# rpi-adapter-board.net
KiCad netlist of a schematic drawn in EasyEDA Pro
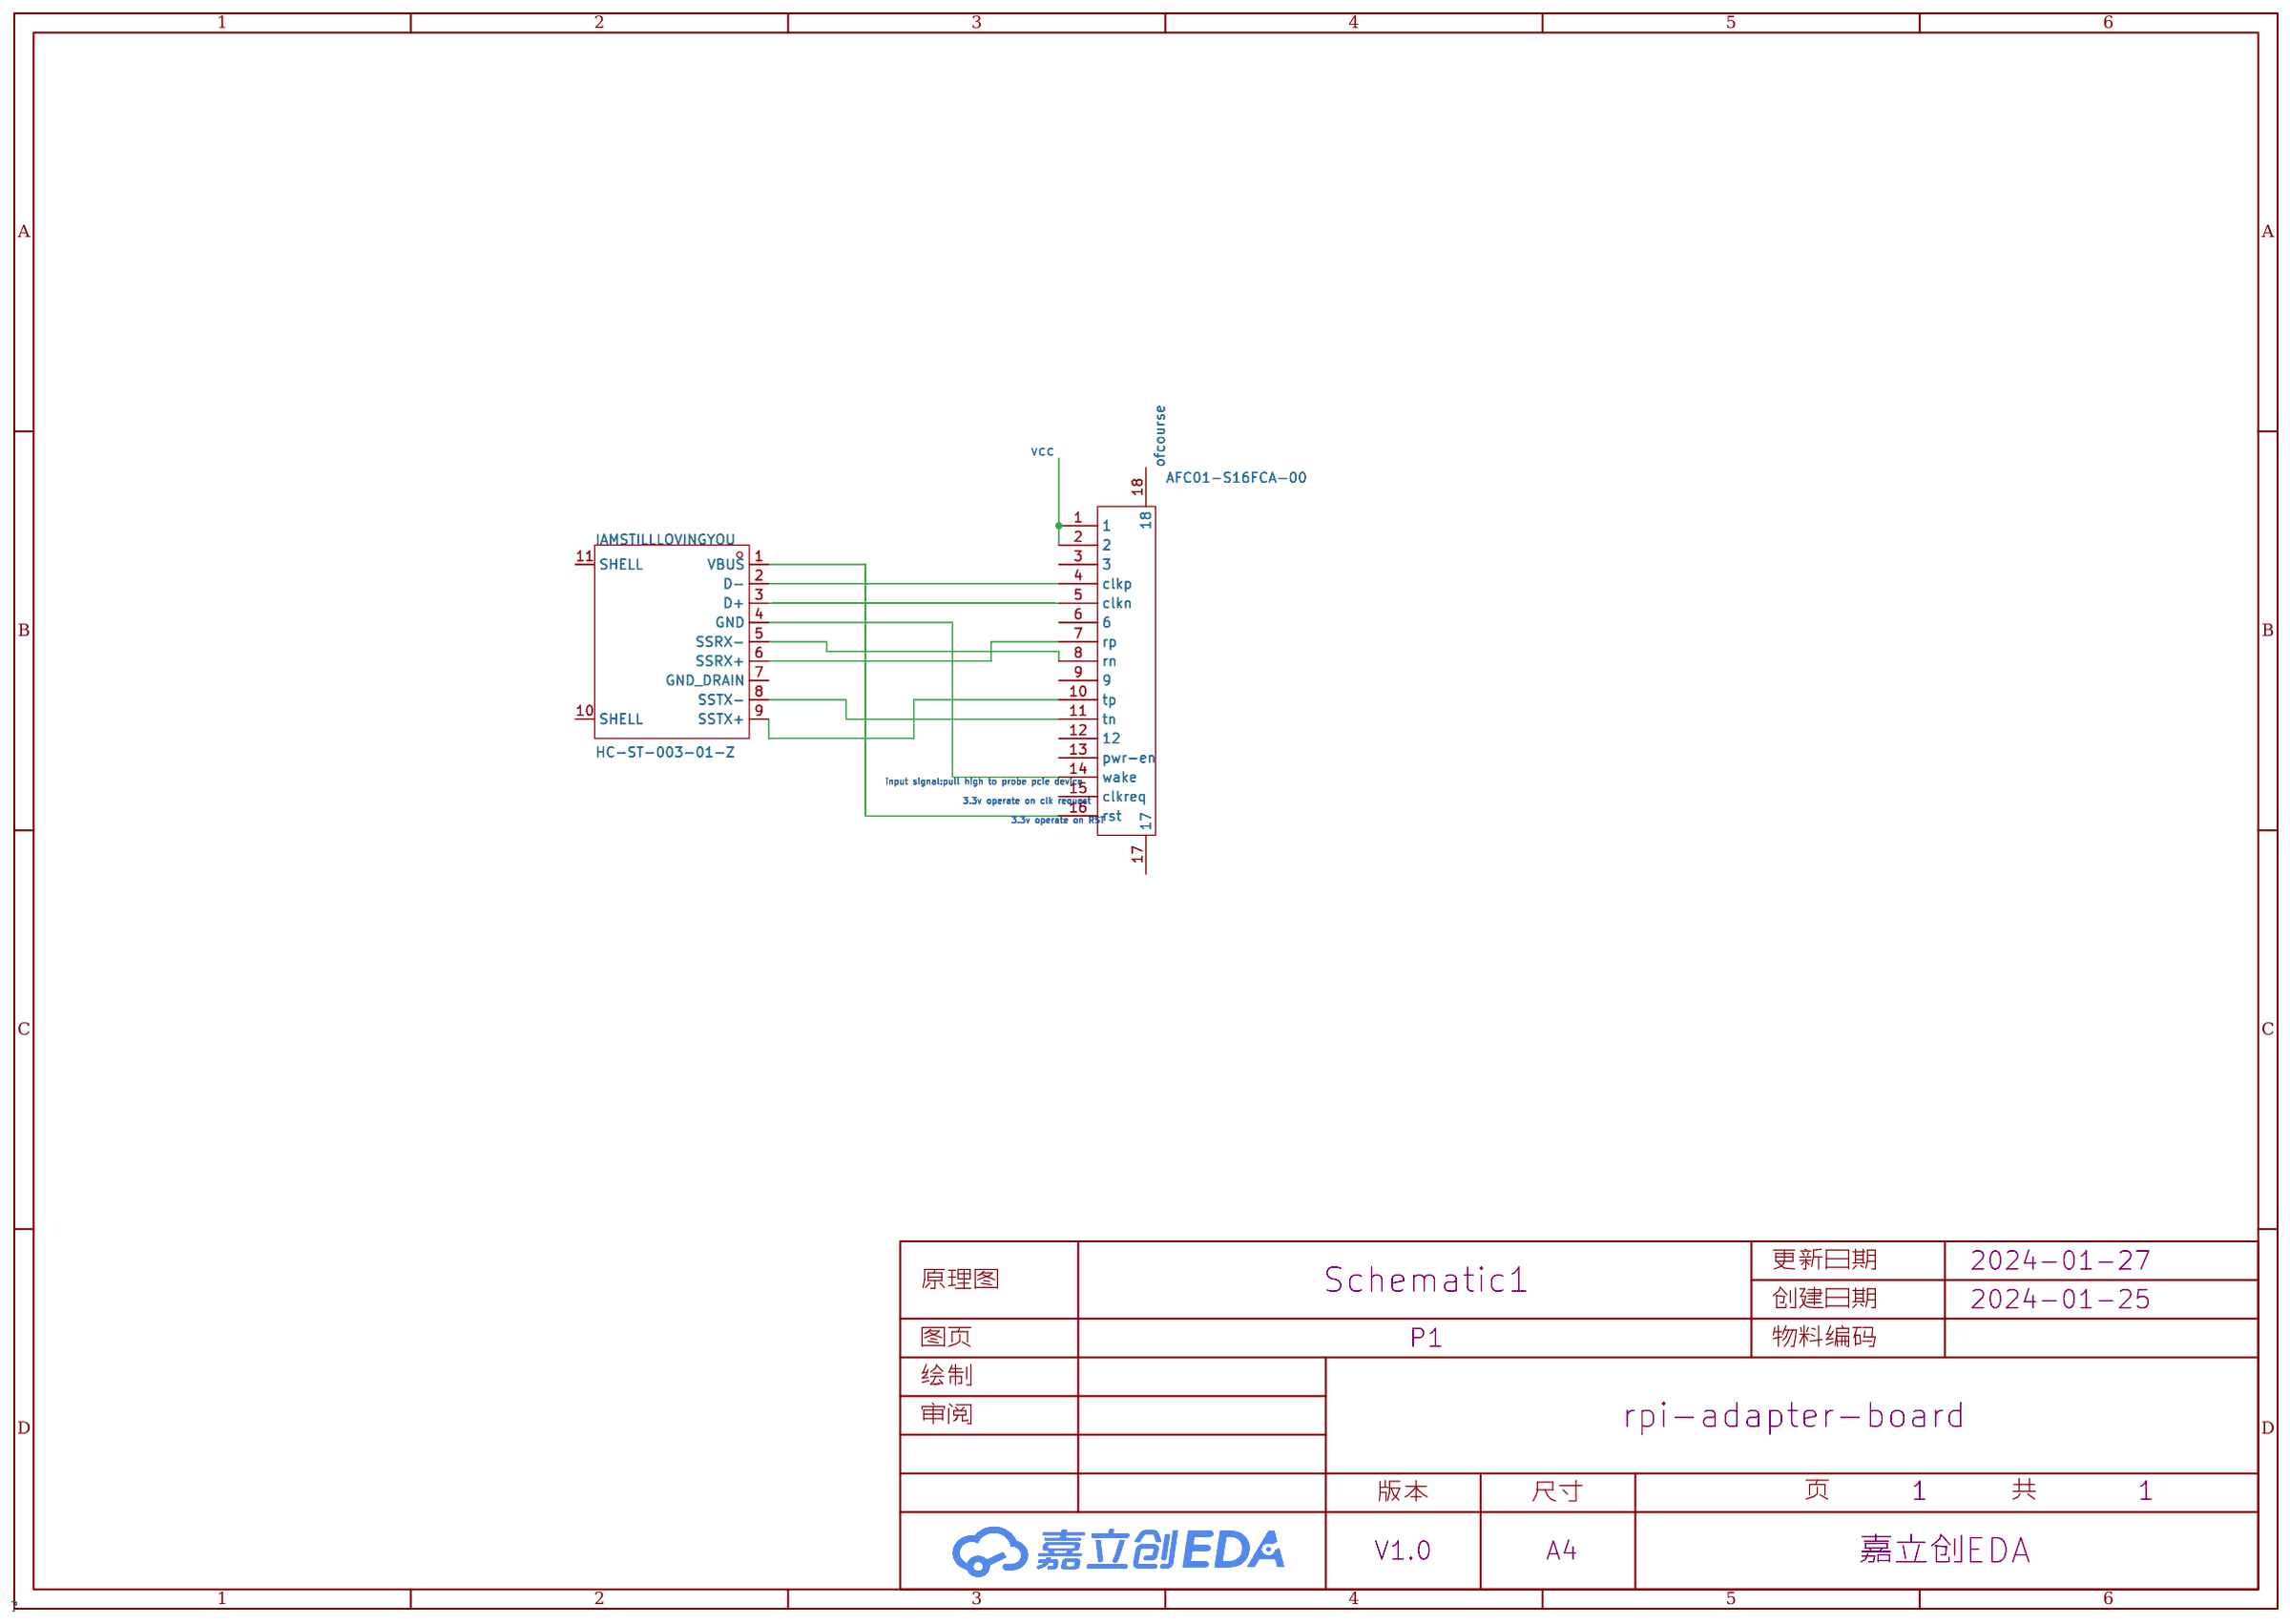
[diagram p0: schematic sheet]

(export (version "E")
  (design (tool "Eeschema 10.0.6"))
  (components
    (comp (ref "IAMSTILLLOVINGYOU")
      (value "HC-ST-003-01-Z")
      (footprint "easyedapro:USB-3.0-A-TH_HC-ST-003-01-Z")
      (fields (field (name "Manufacturer") "HCTL(华灿天禄)"))
      (libsource (lib "easyedapro") (part "HC-ST-003-01-Z"))
    )
    (comp (ref "ofcourse")
      (value "AFC01-S16FCA-00")
      (footprint "easyedapro:FPC-SMD_P0.50-16P_FGS-XJ-H2.0")
      (description "锁定特性:翻盖式;触点类型:下接;触点数量:16P;间距:0.5mm;安装类型:卧贴;")
      (fields (field (name "Manufacturer") "JS(钜硕电子)"))
      (libsource (lib "easyedapro") (part "AFC01-S16FCA-00"))
    )
  )
  (nets
    (net (code "1") (name "Net-(IAMSTILLLOVINGYOU-D+)") (class "Default")
      (node (ref "IAMSTILLLOVINGYOU") (pin "3") (pinfunction "D+_3") (pintype "unspecified"))
      (node (ref "ofcourse") (pin "5") (pinfunction "clkn_5") (pintype "unspecified"))
    )
    (net (code "2") (name "Net-(IAMSTILLLOVINGYOU-D-)") (class "Default")
      (node (ref "IAMSTILLLOVINGYOU") (pin "2") (pinfunction "D-_2") (pintype "unspecified"))
      (node (ref "ofcourse") (pin "4") (pinfunction "clkp_4") (pintype "unspecified"))
    )
    (net (code "3") (name "Net-(IAMSTILLLOVINGYOU-GND)") (class "Default")
      (node (ref "IAMSTILLLOVINGYOU") (pin "4") (pinfunction "GND_4") (pintype "unspecified"))
      (node (ref "ofcourse") (pin "14") (pinfunction "wake_14") (pintype "unspecified"))
    )
    (net (code "4") (name "Net-(IAMSTILLLOVINGYOU-SSRX+)") (class "Default")
      (node (ref "IAMSTILLLOVINGYOU") (pin "6") (pinfunction "SSRX+_6") (pintype "unspecified"))
      (node (ref "ofcourse") (pin "7") (pinfunction "rp_7") (pintype "unspecified"))
    )
    (net (code "5") (name "Net-(IAMSTILLLOVINGYOU-SSRX-)") (class "Default")
      (node (ref "IAMSTILLLOVINGYOU") (pin "5") (pinfunction "SSRX-_5") (pintype "unspecified"))
      (node (ref "ofcourse") (pin "8") (pinfunction "rn_8") (pintype "unspecified"))
    )
    (net (code "6") (name "Net-(IAMSTILLLOVINGYOU-SSTX+)") (class "Default")
      (node (ref "IAMSTILLLOVINGYOU") (pin "9") (pinfunction "SSTX+_9") (pintype "unspecified"))
      (node (ref "ofcourse") (pin "10") (pinfunction "tp_10") (pintype "unspecified"))
    )
    (net (code "7") (name "Net-(IAMSTILLLOVINGYOU-SSTX-)") (class "Default")
      (node (ref "IAMSTILLLOVINGYOU") (pin "8") (pinfunction "SSTX-_8") (pintype "unspecified"))
      (node (ref "ofcourse") (pin "11") (pinfunction "tn_11") (pintype "unspecified"))
    )
    (net (code "8") (name "Net-(IAMSTILLLOVINGYOU-VBUS)") (class "Default")
      (node (ref "IAMSTILLLOVINGYOU") (pin "1") (pinfunction "VBUS_1") (pintype "unspecified"))
      (node (ref "ofcourse") (pin "16") (pinfunction "rst_16") (pintype "unspecified"))
    )
    (net (code "9") (name "Net-(ofcourse-Pad1)") (class "Default")
      (node (ref "ofcourse") (pin "1") (pinfunction "1_1") (pintype "unspecified"))
      (node (ref "ofcourse") (pin "2") (pinfunction "2_2") (pintype "unspecified"))
    )
    (net (code "10") (name "unconnected-(IAMSTILLLOVINGYOU-GND_DRAIN-Pad7)") (class "Default")
      (node (ref "IAMSTILLLOVINGYOU") (pin "7") (pinfunction "GND_DRAIN_7") (pintype "unspecified"))
    )
    (net (code "11") (name "unconnected-(IAMSTILLLOVINGYOU-SHELL-Pad10)") (class "Default")
      (node (ref "IAMSTILLLOVINGYOU") (pin "10") (pinfunction "SHELL_10") (pintype "unspecified"))
    )
    (net (code "12") (name "unconnected-(IAMSTILLLOVINGYOU-SHELL-Pad11)") (class "Default")
      (node (ref "IAMSTILLLOVINGYOU") (pin "11") (pinfunction "SHELL_11") (pintype "unspecified"))
    )
    (net (code "13") (name "unconnected-(ofcourse-Pad3)") (class "Default")
      (node (ref "ofcourse") (pin "3") (pinfunction "3_3") (pintype "unspecified"))
    )
    (net (code "14") (name "unconnected-(ofcourse-Pad6)") (class "Default")
      (node (ref "ofcourse") (pin "6") (pinfunction "6_6") (pintype "unspecified"))
    )
    (net (code "15") (name "unconnected-(ofcourse-Pad9)") (class "Default")
      (node (ref "ofcourse") (pin "9") (pinfunction "9_9") (pintype "unspecified"))
    )
    (net (code "16") (name "unconnected-(ofcourse-Pad12)") (class "Default")
      (node (ref "ofcourse") (pin "12") (pinfunction "12_12") (pintype "unspecified"))
    )
    (net (code "17") (name "unconnected-(ofcourse-Pad17)") (class "Default")
      (node (ref "ofcourse") (pin "17") (pinfunction "17_17") (pintype "unspecified"))
    )
    (net (code "18") (name "unconnected-(ofcourse-Pad18)") (class "Default")
      (node (ref "ofcourse") (pin "18") (pinfunction "18_18") (pintype "unspecified"))
    )
    (net (code "19") (name "unconnected-(ofcourse-clkreq-Pad15)") (class "Default")
      (node (ref "ofcourse") (pin "15") (pinfunction "clkreq_15") (pintype "unspecified"))
    )
    (net (code "20") (name "unconnected-(ofcourse-pwr-en-Pad13)") (class "Default")
      (node (ref "ofcourse") (pin "13") (pinfunction "pwr-en_13") (pintype "unspecified"))
    )
  )
)
